# spider_tx5.net
KiCad netlist of a schematic drawn in EAGLE
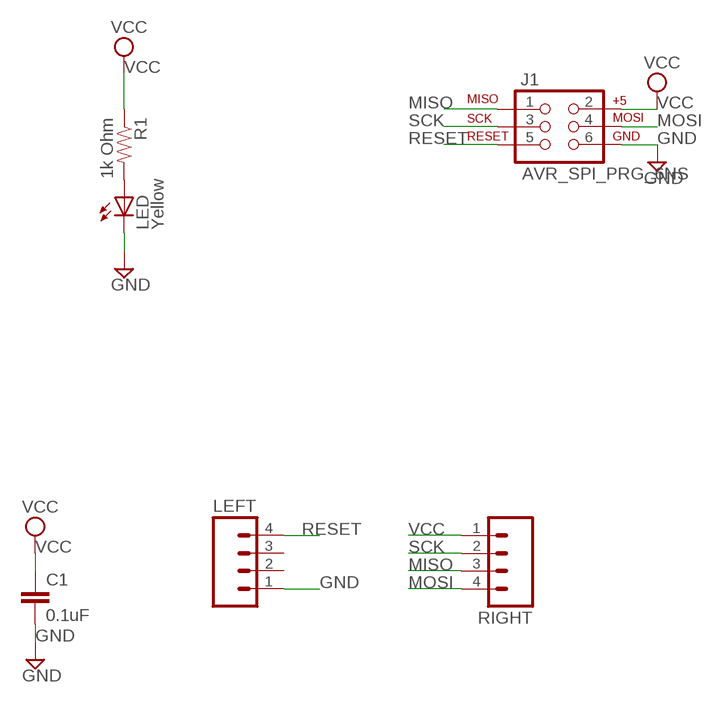
[diagram p0: schematic, sheet 1]

(export (version "E")
  (design (tool "Eeschema 10.0.6"))
  (components
    (comp (ref "C1")
      (value "0.1uF")
      (footprint "eagle-import:1206")
      (libsource (lib "eagle-import") (part "CAP1206"))
    )
    (comp (ref "J1")
      (value "AVR_SPI_PRG_6NS")
      (footprint "eagle-import:2X3-NS")
      (libsource (lib "eagle-import") (part "AVR_SPI_PRG_6NS"))
    )
    (comp (ref "LED")
      (value "Yellow")
      (footprint "eagle-import:LED-1206")
      (libsource (lib "eagle-import") (part "LED-YELLOWLILYPAD"))
    )
    (comp (ref "LEFT")
      (value "M04PTH")
      (footprint "eagle-import:1X04")
      (libsource (lib "eagle-import") (part "M04PTH"))
    )
    (comp (ref "R1")
      (value "1k Ohm")
      (footprint "eagle-import:1206")
      (libsource (lib "eagle-import") (part "RESISTOR1206"))
    )
    (comp (ref "RIGHT")
      (value "M04PTH")
      (footprint "eagle-import:1X04")
      (libsource (lib "eagle-import") (part "M04PTH"))
    )
  )
  (nets
    (net (code "1") (name "/MISO") (class "Default")
      (node (ref "J1") (pin "1") (pinfunction "1_1") (pintype "passive"))
      (node (ref "RIGHT") (pin "3") (pinfunction "3_3") (pintype "passive"))
    )
    (net (code "2") (name "/MOSI") (class "Default")
      (node (ref "J1") (pin "4") (pinfunction "4_4") (pintype "passive"))
      (node (ref "RIGHT") (pin "4") (pinfunction "4_4") (pintype "passive"))
    )
    (net (code "3") (name "/RESET") (class "Default")
      (node (ref "J1") (pin "5") (pinfunction "5_5") (pintype "passive"))
      (node (ref "LEFT") (pin "4") (pinfunction "4_4") (pintype "passive"))
    )
    (net (code "4") (name "/SCK") (class "Default")
      (node (ref "J1") (pin "3") (pinfunction "3_3") (pintype "passive"))
      (node (ref "RIGHT") (pin "2") (pinfunction "2_2") (pintype "passive"))
    )
    (net (code "5") (name "GND") (class "Default")
      (node (ref "C1") (pin "2") (pinfunction "2_2") (pintype "passive"))
      (node (ref "J1") (pin "6") (pinfunction "6_6") (pintype "passive"))
      (node (ref "LED") (pin "C") (pinfunction "C_C") (pintype "passive"))
      (node (ref "LEFT") (pin "1") (pinfunction "1_1") (pintype "passive"))
    )
    (net (code "6") (name "Net-(LED-PadA)") (class "Default")
      (node (ref "LED") (pin "A") (pinfunction "A_A") (pintype "passive"))
      (node (ref "R1") (pin "2") (pinfunction "2_2") (pintype "passive"))
    )
    (net (code "7") (name "VCC") (class "Default")
      (node (ref "C1") (pin "1") (pinfunction "1_1") (pintype "passive"))
      (node (ref "J1") (pin "2") (pinfunction "2_2") (pintype "passive"))
      (node (ref "R1") (pin "1") (pinfunction "1_1") (pintype "passive"))
      (node (ref "RIGHT") (pin "1") (pinfunction "1_1") (pintype "passive"))
    )
    (net (code "8") (name "unconnected-(LEFT-Pad2)") (class "Default")
      (node (ref "LEFT") (pin "2") (pinfunction "2_2") (pintype "passive"))
    )
    (net (code "9") (name "unconnected-(LEFT-Pad3)") (class "Default")
      (node (ref "LEFT") (pin "3") (pinfunction "3_3") (pintype "passive"))
    )
  )
)
